# Power.net
KiCad netlist of a schematic drawn in Altium Designer
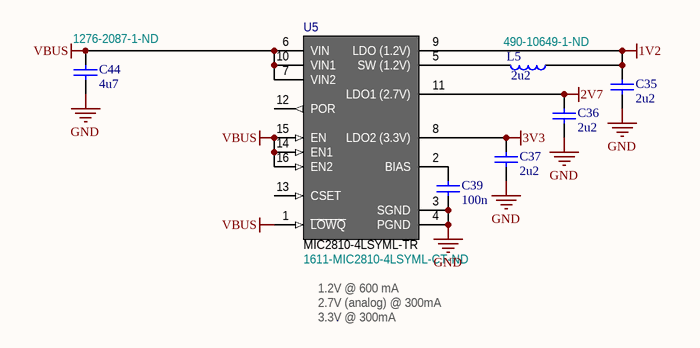
[diagram p0: Power.SchDoc]

(export (version "E")
  (design (tool "Eeschema 10.0.6"))
  (components
    (comp (ref "C35")
      (value "2u2")
      (footprint "CAPC1005N")
      (description "Capacitor (Semiconductor SIM Model)")
      (fields (field (name "PUBLISHER") "Altium Limited"))
      (libsource (lib "Miscellaneous Devices") (part "Cap Semi"))
    )
    (comp (ref "C36")
      (value "2u2")
      (footprint "CAPC1005N")
      (description "Capacitor (Semiconductor SIM Model)")
      (fields (field (name "PUBLISHER") "Altium Limited"))
      (libsource (lib "Miscellaneous Devices") (part "Cap Semi"))
    )
    (comp (ref "C37")
      (value "2u2")
      (footprint "CAPC1005N")
      (description "Capacitor (Semiconductor SIM Model)")
      (fields (field (name "PUBLISHER") "Altium Limited"))
      (libsource (lib "Miscellaneous Devices") (part "Cap Semi"))
    )
    (comp (ref "C39")
      (value "100n")
      (footprint "CAPC0603N")
      (description "Capacitor (Semiconductor SIM Model)")
      (fields (field (name "PUBLISHER") "Altium Limited"))
      (libsource (lib "Miscellaneous Devices") (part "Cap Semi"))
    )
    (comp (ref "C44")
      (value "4u7")
      (footprint "CAPC1608N")
      (description "Capacitor (Semiconductor SIM Model)")
      (fields
        (field (name "SUPPLIER PART NUMBER 1") "1276-2087-1-ND")
        (field (name "PUBLISHER") "Altium Limited")
      )
      (libsource (lib "Miscellaneous Devices") (part "Cap Semi"))
    )
    (comp (ref "L5")
      (value "2u2")
      (footprint "INDC2520X12N")
      (description "Inductor")
      (fields
        (field (name "SUPPLIER PART NUMBER 1") "490-10649-1-ND")
        (field (name "PUBLISHER") "Altium Limited")
      )
      (libsource (lib "Miscellaneous Devices") (part "Inductor"))
    )
    (comp (ref "U5")
      (value "MIC2810-4LSYML-TR")
      (footprint "QFN50P300X300X90-16N")
      (description "IC REG TRPL BUCK/LINEAR 16-MLF")
      (fields
        (field (name "MANUFACTURER") "Microchip Technology")
        (field (name "SUPPLIER PART NUMBER 1") "1611-MIC2810-4LSYML-CT-ND")
      )
      (libsource (lib "Microchip PMIC") (part "MIC2810-4LSYML-TR"))
    )
  )
  (nets
    (net (code "1") (name "1V2") (class "Default")
      (node (ref "C35") (pin "2") (pinfunction "2_2") (pintype "passive"))
      (node (ref "L5") (pin "1") (pinfunction "1_1") (pintype "passive"))
      (node (ref "U5") (pin "9") (pinfunction "LDO_(1.2V)_9") (pintype "power_in"))
    )
    (net (code "2") (name "2V7") (class "Default")
      (node (ref "C36") (pin "2") (pinfunction "2_2") (pintype "passive"))
      (node (ref "U5") (pin "11") (pinfunction "LDO1_(2.7V)_11") (pintype "power_in"))
    )
    (net (code "3") (name "3V3") (class "Default")
      (node (ref "C37") (pin "2") (pinfunction "2_2") (pintype "passive"))
      (node (ref "U5") (pin "8") (pinfunction "LDO2_(3.3V)_8") (pintype "power_in"))
    )
    (net (code "4") (name "GND") (class "Default")
      (node (ref "C35") (pin "1") (pinfunction "1_1") (pintype "passive"))
      (node (ref "C36") (pin "1") (pinfunction "1_1") (pintype "passive"))
      (node (ref "C37") (pin "1") (pinfunction "1_1") (pintype "passive"))
      (node (ref "C39") (pin "2") (pinfunction "2_2") (pintype "passive"))
      (node (ref "C44") (pin "1") (pinfunction "1_1") (pintype "passive"))
      (node (ref "U5") (pin "3") (pinfunction "SGND_3") (pintype "power_in"))
      (node (ref "U5") (pin "4") (pinfunction "PGND_4") (pintype "power_in"))
    )
    (net (code "5") (name "Net-(U5-BIAS)") (class "Default")
      (node (ref "C39") (pin "1") (pinfunction "1_1") (pintype "passive"))
      (node (ref "U5") (pin "2") (pinfunction "BIAS_2") (pintype "power_in"))
    )
    (net (code "6") (name "Net-(U5-SW_(1.2V))") (class "Default")
      (node (ref "L5") (pin "2") (pinfunction "2_2") (pintype "passive"))
      (node (ref "U5") (pin "5") (pinfunction "SW_(1.2V)_5") (pintype "power_in"))
    )
    (net (code "7") (name "VBUS") (class "Default")
      (node (ref "C44") (pin "2") (pinfunction "2_2") (pintype "passive"))
      (node (ref "U5") (pin "1") (pinfunction "~{LOWQ}_1") (pintype "input"))
      (node (ref "U5") (pin "10") (pinfunction "VIN1_10") (pintype "power_in"))
      (node (ref "U5") (pin "14") (pinfunction "EN1_14") (pintype "input"))
      (node (ref "U5") (pin "15") (pinfunction "EN_15") (pintype "input"))
      (node (ref "U5") (pin "16") (pinfunction "EN2_16") (pintype "input"))
      (node (ref "U5") (pin "6") (pinfunction "VIN_6") (pintype "power_in"))
      (node (ref "U5") (pin "7") (pinfunction "VIN2_7") (pintype "power_in"))
    )
    (net (code "8") (name "unconnected-(U5-CSET-Pad13)") (class "Default")
      (node (ref "U5") (pin "13") (pinfunction "CSET_13") (pintype "input"))
    )
    (net (code "9") (name "unconnected-(U5-POR-Pad12)") (class "Default")
      (node (ref "U5") (pin "12") (pinfunction "POR_12") (pintype "output"))
    )
  )
)
